# 2.net
KiCad netlist of a schematic drawn in Altium Designer
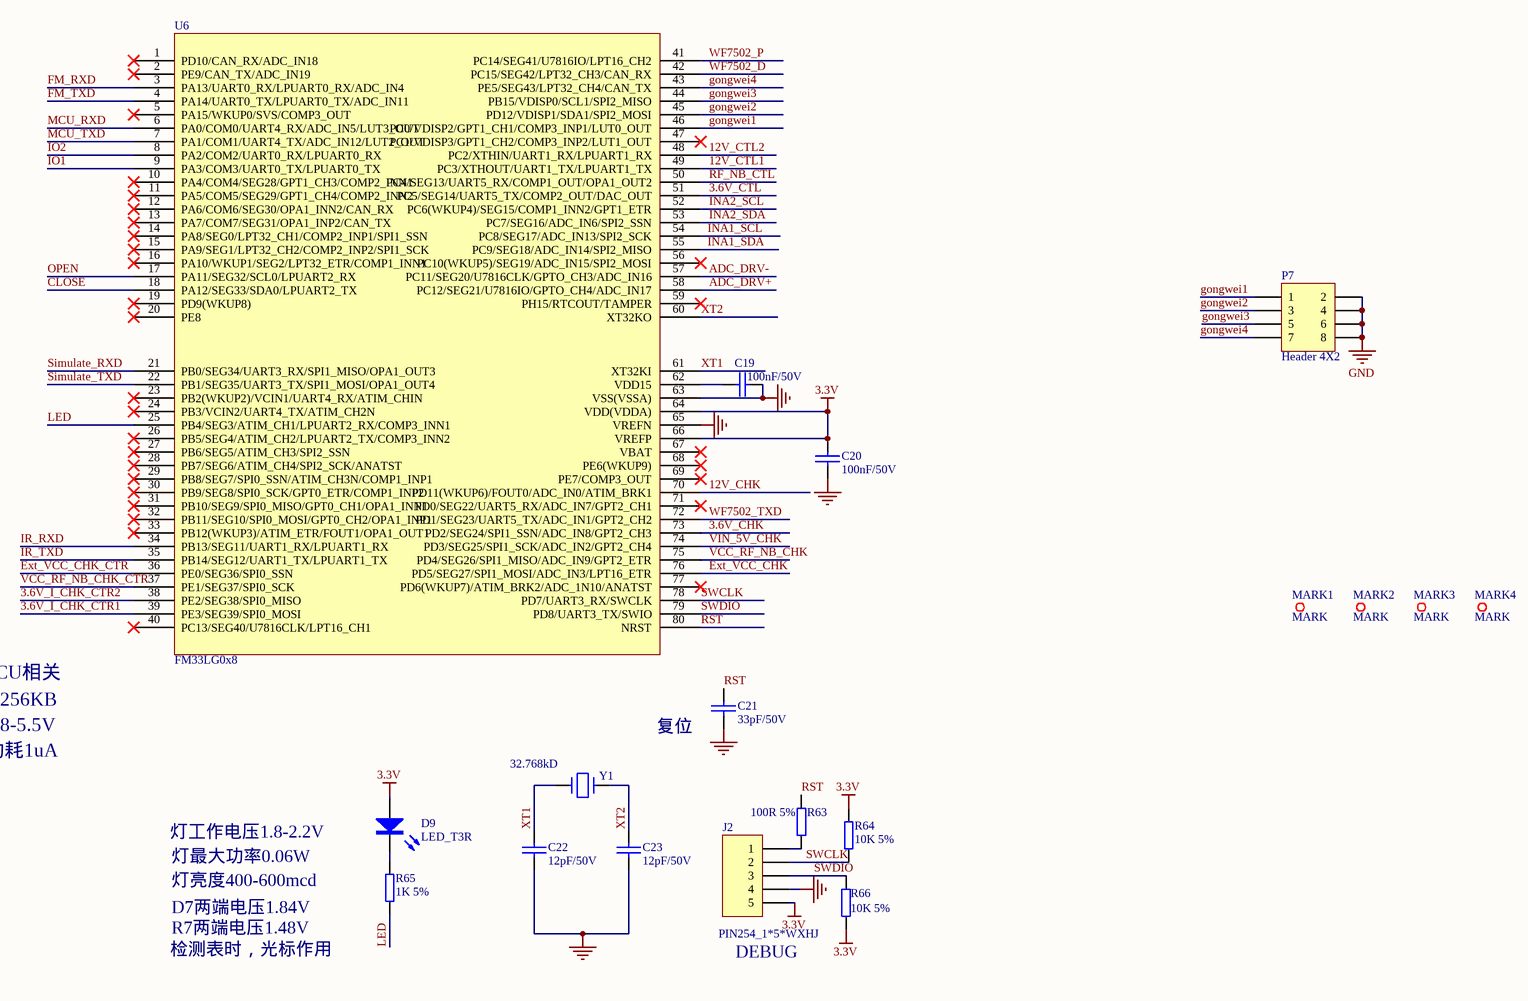
[diagram p0: 水表通用工装一版2.SchDoc]

(export (version "E")
  (design (tool "Eeschema 10.0.6"))
  (components
    (comp (ref "C19")
      (value "100nF/50V")
      (footprint "CAP0603")
      (description "104pF,50 V,±10%,0603,国巨,CC0603KRX7R9BB104")
      (fields (field (name "PART NUMBER") "101020103-0021"))
      (libsource (lib "Database_Libs2") (part "CC03K7R9_100N"))
    )
    (comp (ref "C20")
      (value "100nF/50V")
      (footprint "CAP0603")
      (description "104pF,50 V,±10%,0603,国巨,CC0603KRX7R9BB104")
      (fields (field (name "PART NUMBER") "101020103-0021"))
      (libsource (lib "Database_Libs2") (part "CC03K7R9_100N"))
    )
    (comp (ref "C21")
      (value "33pF/50V")
      (footprint "CAP0603")
      (description "33pF,50 V,±10%,0603,国巨,CC0603KRNPO9BN33")
      (fields (field (name "PART NUMBER") "101020103-0027"))
      (libsource (lib "Database_Libs2") (part "CC03KPO9_33P"))
    )
    (comp (ref "C22")
      (value "12pF/50V")
      (footprint "CAP0603")
      (description "12P,50 V,±5%,0603,国巨,CC0603JRNPO9BN12")
      (fields (field (name "PART NUMBER") "101020103-0005"))
      (libsource (lib "Database_Libs2") (part "CC03JPO9_12P"))
    )
    (comp (ref "C23")
      (value "12pF/50V")
      (footprint "CAP0603")
      (description "12P,50 V,±5%,0603,国巨,CC0603JRNPO9BN12")
      (fields (field (name "PART NUMBER") "101020103-0005"))
      (libsource (lib "Database_Libs2") (part "CC03JPO9_12P"))
    )
    (comp (ref "D9")
      (value "LED_T3R")
      (footprint "LED2_300")
      (description "圆形插件,3mm 圆形,插件,红光,湖北匡通电子有限公司,3BB4HC")
      (fields (field (name "PART NUMBER") "101040102-0001"))
      (libsource (lib "Database_Libs2") (part "01-LED_T3R"))
    )
    (comp (ref "J2")
      (value "PIN254_1*5*WXHJ")
      (footprint "PIN254_1*5*1100S")
      (description "1*5 ，Φ1.0 ，2.54mm，直脚,无需焊接器件")
      (fields (field (name "PART NUMBER") "AD_WXHJ_PinHeader_02"))
      (libsource (lib "Database_Libs2") (part "PIN254_1*5*1100S"))
    )
    (comp (ref "MARK1")
      (value "MARK")
      (footprint "MARK")
      (description "MARK点")
      (fields (field (name "PART NUMBER") "AD_WXHJ_MARK_01"))
      (libsource (lib "转接板封装") (part "MARK"))
    )
    (comp (ref "MARK2")
      (value "MARK")
      (footprint "MARK")
      (description "MARK点")
      (fields (field (name "PART NUMBER") "AD_WXHJ_MARK_01"))
      (libsource (lib "转接板封装") (part "MARK"))
    )
    (comp (ref "MARK3")
      (value "MARK")
      (footprint "MARK")
      (description "MARK点")
      (fields (field (name "PART NUMBER") "AD_WXHJ_MARK_01"))
      (libsource (lib "转接板封装") (part "MARK"))
    )
    (comp (ref "MARK4")
      (value "MARK")
      (footprint "MARK")
      (description "MARK点")
      (fields (field (name "PART NUMBER") "AD_WXHJ_MARK_01"))
      (libsource (lib "转接板封装") (part "MARK"))
    )
    (comp (ref "P7")
      (value "Header 4X2")
      (footprint "HDR2X4")
      (description "Header, 4-Pin, Dual row")
      (libsource (lib "CBB_Lib_SCH") (part "Header 4X2"))
    )
    (comp (ref "R63")
      (value "100R 5%")
      (footprint "RES0603")
      (description "100R,±5%,1/10W,0603,国巨,RC0603JR-07100RL")
      (fields (field (name "PART NUMBER") "101010103-0022"))
      (libsource (lib "Database_Libs2") (part "RC03J_100R"))
    )
    (comp (ref "R64")
      (value "10K 5%")
      (footprint "RES0603")
      (description "国巨,±5%,0603,,155 ℃,-55 ℃,RC0603JR-0710KL,无铅,200 ppm/℃,1/10W,,10K")
      (fields (field (name "PART NUMBER") "101010103-0003"))
      (libsource (lib "Database_Libs2") (part "RC03J_10K"))
    )
    (comp (ref "R65")
      (value "1K 5%")
      (footprint "RES0603")
      (description "1K,±5%,1/10W,0603,国巨,RC0603JR-071KL")
      (fields (field (name "PART NUMBER") "101010103-0008"))
      (libsource (lib "Database_Libs2") (part "RC03J_1K"))
    )
    (comp (ref "R66")
      (value "10K 5%")
      (footprint "RES0603")
      (description "国巨,±5%,0603,,155 ℃,-55 ℃,RC0603JR-0710KL,无铅,200 ppm/℃,1/10W,,10K")
      (fields (field (name "PART NUMBER") "101010103-0003"))
      (libsource (lib "Database_Libs2") (part "RC03J_10K"))
    )
    (comp (ref "U6") (value "FM33LG0x8") (footprint "LQFP80") (libsource (lib "FM_MCU") (part "FM33LG0x8")))
    (comp (ref "Y1")
      (value "32.768kD")
      (footprint "SMD-3215_2P")
      (fields (field (name "PART NUMBER") "1010601-0020"))
      (libsource (lib "Database_Libs2") (part "04_XTALSG12MD_32.768kD"))
    )
  )
  (nets
    (net (code "1") (name "/3.6V_CHK") (class "Default")
      (node (ref "U6") (pin "73") (pinfunction "PD2/SEG24/SPI1_SSN/ADC_IN8/GPT2_CH3_73") (pintype "passive"))
    )
    (net (code "2") (name "/3.6V_CTL") (class "Default")
      (node (ref "U6") (pin "51") (pinfunction "PC5/SEG14/UART5_TX/COMP2_OUT/DAC_OUT_51") (pintype "passive"))
    )
    (net (code "3") (name "/3.6V_I_CHK_CTR1") (class "Default")
      (node (ref "U6") (pin "39") (pinfunction "PE3/SEG39/SPI0_MOSI_39") (pintype "passive"))
    )
    (net (code "4") (name "/3.6V_I_CHK_CTR2") (class "Default")
      (node (ref "U6") (pin "38") (pinfunction "PE2/SEG38/SPI0_MISO_38") (pintype "passive"))
    )
    (net (code "5") (name "/12V_CHK") (class "Default")
      (node (ref "U6") (pin "70") (pinfunction "PD11(WKUP6)/FOUT0/ADC_IN0/ATIM_BRK1_70") (pintype "passive"))
    )
    (net (code "6") (name "/12V_CTL1") (class "Default")
      (node (ref "U6") (pin "49") (pinfunction "PC3/XTHOUT/UART1_TX/LPUART1_TX_49") (pintype "passive"))
    )
    (net (code "7") (name "/12V_CTL2") (class "Default")
      (node (ref "U6") (pin "48") (pinfunction "PC2/XTHIN/UART1_RX/LPUART1_RX_48") (pintype "passive"))
    )
    (net (code "8") (name "/ADC_DRV+") (class "Default")
      (node (ref "U6") (pin "58") (pinfunction "PC12/SEG21/U7816IO/GPTO_CH4/ADC_IN17_58") (pintype "passive"))
    )
    (net (code "9") (name "/ADC_DRV-") (class "Default")
      (node (ref "U6") (pin "57") (pinfunction "PC11/SEG20/U7816CLK/GPTO_CH3/ADC_IN16_57") (pintype "passive"))
    )
    (net (code "10") (name "/CLOSE") (class "Default")
      (node (ref "U6") (pin "18") (pinfunction "PA12/SEG33/SDA0/LPUART2_TX_18") (pintype "passive"))
    )
    (net (code "11") (name "/Ext_VCC_CHK") (class "Default")
      (node (ref "U6") (pin "76") (pinfunction "PD5/SEG27/SPI1_MOSI/ADC_IN3/LPT16_ETR_76") (pintype "passive"))
    )
    (net (code "12") (name "/Ext_VCC_CHK_CTR") (class "Default")
      (node (ref "U6") (pin "36") (pinfunction "PE0/SEG36/SPI0_SSN_36") (pintype "passive"))
    )
    (net (code "13") (name "/FM_RXD") (class "Default")
      (node (ref "U6") (pin "3") (pinfunction "PA13/UART0_RX/LPUART0_RX/ADC_IN4_3") (pintype "passive"))
    )
    (net (code "14") (name "/FM_TXD") (class "Default")
      (node (ref "U6") (pin "4") (pinfunction "PA14/UART0_TX/LPUART0_TX/ADC_IN11_4") (pintype "passive"))
    )
    (net (code "15") (name "/INA1_SCL") (class "Default")
      (node (ref "U6") (pin "54") (pinfunction "PC8/SEG17/ADC_IN13/SPI2_SCK_54") (pintype "passive"))
    )
    (net (code "16") (name "/INA1_SDA") (class "Default")
      (node (ref "U6") (pin "55") (pinfunction "PC9/SEG18/ADC_IN14/SPI2_MISO_55") (pintype "passive"))
    )
    (net (code "17") (name "/INA2_SCL") (class "Default")
      (node (ref "U6") (pin "52") (pinfunction "PC6(WKUP4)/SEG15/COMP1_INN2/GPT1_ETR_52") (pintype "passive"))
    )
    (net (code "18") (name "/INA2_SDA") (class "Default")
      (node (ref "U6") (pin "53") (pinfunction "PC7/SEG16/ADC_IN6/SPI2_SSN_53") (pintype "passive"))
    )
    (net (code "19") (name "/IO1") (class "Default")
      (node (ref "U6") (pin "9") (pinfunction "PA3/COM3/UART0_TX/LPUART0_TX_9") (pintype "passive"))
    )
    (net (code "20") (name "/IO2") (class "Default")
      (node (ref "U6") (pin "8") (pinfunction "PA2/COM2/UART0_RX/LPUART0_RX_8") (pintype "passive"))
    )
    (net (code "21") (name "/IR_RXD") (class "Default")
      (node (ref "U6") (pin "34") (pinfunction "PB13/SEG11/UART1_RX/LPUART1_RX_34") (pintype "passive"))
    )
    (net (code "22") (name "/IR_TXD") (class "Default")
      (node (ref "U6") (pin "35") (pinfunction "PB14/SEG12/UART1_TX/LPUART1_TX_35") (pintype "passive"))
    )
    (net (code "23") (name "/LED") (class "Default")
      (node (ref "R65") (pin "1") (pinfunction "1_1") (pintype "passive"))
      (node (ref "U6") (pin "25") (pinfunction "PB4/SEG3/ATIM_CH1/LPUART2_RX/COMP3_INN1_25") (pintype "passive"))
    )
    (net (code "24") (name "/MCU_RXD") (class "Default")
      (node (ref "U6") (pin "6") (pinfunction "PA0/COM0/UART4_RX/ADC_IN5/LUT3_OUT_6") (pintype "passive"))
    )
    (net (code "25") (name "/MCU_TXD") (class "Default")
      (node (ref "U6") (pin "7") (pinfunction "PA1/COM1/UART4_TX/ADC_IN12/LUT2_OUT_7") (pintype "passive"))
    )
    (net (code "26") (name "/OPEN") (class "Default")
      (node (ref "U6") (pin "17") (pinfunction "PA11/SEG32/SCL0/LPUART2_RX_17") (pintype "passive"))
    )
    (net (code "27") (name "/RF_NB_CTL") (class "Default")
      (node (ref "U6") (pin "50") (pinfunction "PC4/SEG13/UART5_RX/COMP1_OUT/OPA1_OUT2_50") (pintype "passive"))
    )
    (net (code "28") (name "/RST") (class "Default")
      (node (ref "C21") (pin "1") (pinfunction "1_1") (pintype "passive"))
      (node (ref "R63") (pin "1") (pinfunction "1_1") (pintype "passive"))
      (node (ref "U6") (pin "80") (pinfunction "NRST_80") (pintype "passive"))
    )
    (net (code "29") (name "/SWCLK") (class "Default")
      (node (ref "J2") (pin "2") (pinfunction "2_2") (pintype "passive"))
      (node (ref "R64") (pin "2") (pinfunction "2_2") (pintype "passive"))
      (node (ref "U6") (pin "78") (pinfunction "PD7/UART3_RX/SWCLK_78") (pintype "passive"))
    )
    (net (code "30") (name "/SWDIO") (class "Default")
      (node (ref "J2") (pin "3") (pinfunction "3_3") (pintype "passive"))
      (node (ref "R66") (pin "2") (pinfunction "2_2") (pintype "passive"))
      (node (ref "U6") (pin "79") (pinfunction "PD8/UART3_TX/SWIO_79") (pintype "passive"))
    )
    (net (code "31") (name "/Simulate_RXD") (class "Default")
      (node (ref "U6") (pin "21") (pinfunction "PB0/SEG34/UART3_RX/SPI1_MISO/OPA1_OUT3_21") (pintype "passive"))
    )
    (net (code "32") (name "/Simulate_TXD") (class "Default")
      (node (ref "U6") (pin "22") (pinfunction "PB1/SEG35/UART3_TX/SPI1_MOSI/OPA1_OUT4_22") (pintype "passive"))
    )
    (net (code "33") (name "/VCC_RF_NB_CHK") (class "Default")
      (node (ref "U6") (pin "75") (pinfunction "PD4/SEG26/SPI1_MISO/ADC_IN9/GPT2_ETR_75") (pintype "passive"))
    )
    (net (code "34") (name "/VCC_RF_NB_CHK_CTR") (class "Default")
      (node (ref "U6") (pin "37") (pinfunction "PE1/SEG37/SPI0_SCK_37") (pintype "passive"))
    )
    (net (code "35") (name "/VIN_5V_CHK") (class "Default")
      (node (ref "U6") (pin "74") (pinfunction "PD3/SEG25/SPI1_SCK/ADC_IN2/GPT2_CH4_74") (pintype "passive"))
    )
    (net (code "36") (name "/WF7502_D") (class "Default")
      (node (ref "U6") (pin "42") (pinfunction "PC15/SEG42/LPT32_CH3/CAN_RX_42") (pintype "passive"))
    )
    (net (code "37") (name "/WF7502_P") (class "Default")
      (node (ref "U6") (pin "41") (pinfunction "PC14/SEG41/U7816IO/LPT16_CH2_41") (pintype "passive"))
    )
    (net (code "38") (name "/WF7502_TXD") (class "Default")
      (node (ref "U6") (pin "72") (pinfunction "PD1/SEG23/UART5_TX/ADC_IN1/GPT2_CH2_72") (pintype "passive"))
    )
    (net (code "39") (name "/XT1") (class "Default")
      (node (ref "C22") (pin "1") (pinfunction "1_1") (pintype "passive"))
      (node (ref "U6") (pin "61") (pinfunction "XT32KI_61") (pintype "passive"))
      (node (ref "Y1") (pin "1") (pinfunction "1_1") (pintype "passive"))
    )
    (net (code "40") (name "/XT2") (class "Default")
      (node (ref "C23") (pin "2") (pinfunction "2_2") (pintype "passive"))
      (node (ref "U6") (pin "60") (pinfunction "XT32KO_60") (pintype "passive"))
      (node (ref "Y1") (pin "2") (pinfunction "2_2") (pintype "passive"))
    )
    (net (code "41") (name "/gongwei1") (class "Default")
      (node (ref "P7") (pin "1") (pinfunction "1_1") (pintype "passive"))
      (node (ref "U6") (pin "46") (pinfunction "PC0/VDISP2/GPT1_CH1/COMP3_INP1/LUT0_OUT_46") (pintype "passive"))
    )
    (net (code "42") (name "/gongwei2") (class "Default")
      (node (ref "P7") (pin "3") (pinfunction "3_3") (pintype "passive"))
      (node (ref "U6") (pin "45") (pinfunction "PD12/VDISP1/SDA1/SPI2_MOSI_45") (pintype "passive"))
    )
    (net (code "43") (name "/gongwei3") (class "Default")
      (node (ref "P7") (pin "5") (pinfunction "5_5") (pintype "passive"))
      (node (ref "U6") (pin "44") (pinfunction "PB15/VDISP0/SCL1/SPI2_MISO_44") (pintype "passive"))
    )
    (net (code "44") (name "/gongwei4") (class "Default")
      (node (ref "P7") (pin "7") (pinfunction "7_7") (pintype "passive"))
      (node (ref "U6") (pin "43") (pinfunction "PE5/SEG43/LPT32_CH4/CAN_TX_43") (pintype "passive"))
    )
    (net (code "45") (name "3.3V") (class "Default")
      (node (ref "C20") (pin "2") (pinfunction "2_2") (pintype "passive"))
      (node (ref "D9") (pin "1") (pinfunction "1_1") (pintype "passive"))
      (node (ref "J2") (pin "5") (pinfunction "5_5") (pintype "passive"))
      (node (ref "R64") (pin "1") (pinfunction "1_1") (pintype "passive"))
      (node (ref "R66") (pin "1") (pinfunction "1_1") (pintype "passive"))
      (node (ref "U6") (pin "64") (pinfunction "VDD(VDDA)_64") (pintype "passive"))
      (node (ref "U6") (pin "66") (pinfunction "VREFP_66") (pintype "passive"))
    )
    (net (code "46") (name "GND") (class "Default")
      (node (ref "C19") (pin "2") (pinfunction "2_2") (pintype "passive"))
      (node (ref "C20") (pin "1") (pinfunction "1_1") (pintype "passive"))
      (node (ref "C21") (pin "2") (pinfunction "2_2") (pintype "passive"))
      (node (ref "C22") (pin "2") (pinfunction "2_2") (pintype "passive"))
      (node (ref "C23") (pin "1") (pinfunction "1_1") (pintype "passive"))
      (node (ref "J2") (pin "4") (pinfunction "4_4") (pintype "passive"))
      (node (ref "P7") (pin "2") (pinfunction "2_2") (pintype "passive"))
      (node (ref "P7") (pin "4") (pinfunction "4_4") (pintype "passive"))
      (node (ref "P7") (pin "6") (pinfunction "6_6") (pintype "passive"))
      (node (ref "P7") (pin "8") (pinfunction "8_8") (pintype "passive"))
      (node (ref "U6") (pin "63") (pinfunction "VSS(VSSA)_63") (pintype "passive"))
      (node (ref "U6") (pin "65") (pinfunction "VREFN_65") (pintype "passive"))
    )
    (net (code "47") (name "Net-(D9-Pad2)") (class "Default")
      (node (ref "D9") (pin "2") (pinfunction "2_2") (pintype "passive"))
      (node (ref "R65") (pin "2") (pinfunction "2_2") (pintype "passive"))
    )
    (net (code "48") (name "Net-(J2-Pad1)") (class "Default")
      (node (ref "J2") (pin "1") (pinfunction "1_1") (pintype "passive"))
      (node (ref "R63") (pin "2") (pinfunction "2_2") (pintype "passive"))
    )
    (net (code "49") (name "Net-(U6-VDD15)") (class "Default")
      (node (ref "C19") (pin "1") (pinfunction "1_1") (pintype "passive"))
      (node (ref "U6") (pin "62") (pinfunction "VDD15_62") (pintype "passive"))
    )
    (net (code "50") (name "unconnected-(U6-PA4{slash}COM4{slash}SEG28{slash}GPT1_CH3{slash}COMP2_INN1-Pad10)") (class "Default")
      (node (ref "U6") (pin "10") (pinfunction "PA4/COM4/SEG28/GPT1_CH3/COMP2_INN1_10") (pintype "passive+no_connect"))
    )
    (net (code "51") (name "unconnected-(U6-PA5{slash}COM5{slash}SEG29{slash}GPT1_CH4{slash}COMP2_INN2-Pad11)") (class "Default")
      (node (ref "U6") (pin "11") (pinfunction "PA5/COM5/SEG29/GPT1_CH4/COMP2_INN2_11") (pintype "passive+no_connect"))
    )
    (net (code "52") (name "unconnected-(U6-PA6{slash}COM6{slash}SEG30{slash}OPA1_INN2{slash}CAN_RX-Pad12)") (class "Default")
      (node (ref "U6") (pin "12") (pinfunction "PA6/COM6/SEG30/OPA1_INN2/CAN_RX_12") (pintype "passive+no_connect"))
    )
    (net (code "53") (name "unconnected-(U6-PA7{slash}COM7{slash}SEG31{slash}OPA1_INP2{slash}CAN_TX-Pad13)") (class "Default")
      (node (ref "U6") (pin "13") (pinfunction "PA7/COM7/SEG31/OPA1_INP2/CAN_TX_13") (pintype "passive+no_connect"))
    )
    (net (code "54") (name "unconnected-(U6-PA8{slash}SEG0{slash}LPT32_CH1{slash}COMP2_INP1{slash}SPI1_SSN-Pad14)") (class "Default")
      (node (ref "U6") (pin "14") (pinfunction "PA8/SEG0/LPT32_CH1/COMP2_INP1/SPI1_SSN_14") (pintype "passive+no_connect"))
    )
    (net (code "55") (name "unconnected-(U6-PA9{slash}SEG1{slash}LPT32_CH2{slash}COMP2_INP2{slash}SPI1_SCK-Pad15)") (class "Default")
      (node (ref "U6") (pin "15") (pinfunction "PA9/SEG1/LPT32_CH2/COMP2_INP2/SPI1_SCK_15") (pintype "passive+no_connect"))
    )
    (net (code "56") (name "unconnected-(U6-PA10{slash}WKUP1{slash}SEG2{slash}LPT32_ETR{slash}COMP1_INN1-Pad16)") (class "Default")
      (node (ref "U6") (pin "16") (pinfunction "PA10/WKUP1/SEG2/LPT32_ETR/COMP1_INN1_16") (pintype "passive+no_connect"))
    )
    (net (code "57") (name "unconnected-(U6-PA15{slash}WKUP0{slash}SVS{slash}COMP3_OUT-Pad5)") (class "Default")
      (node (ref "U6") (pin "5") (pinfunction "PA15/WKUP0/SVS/COMP3_OUT_5") (pintype "passive+no_connect"))
    )
    (net (code "58") (name "unconnected-(U6-PB2(WKUP2){slash}VCIN1{slash}UART4_RX{slash}ATIM_CHIN-Pad23)") (class "Default")
      (node (ref "U6") (pin "23") (pinfunction "PB2(WKUP2)/VCIN1/UART4_RX/ATIM_CHIN_23") (pintype "passive+no_connect"))
    )
    (net (code "59") (name "unconnected-(U6-PB3{slash}VCIN2{slash}UART4_TX{slash}ATIM_CH2N-Pad24)") (class "Default")
      (node (ref "U6") (pin "24") (pinfunction "PB3/VCIN2/UART4_TX/ATIM_CH2N_24") (pintype "passive+no_connect"))
    )
    (net (code "60") (name "unconnected-(U6-PB5{slash}SEG4{slash}ATIM_CH2{slash}LPUART2_TX{slash}COMP3_INN2-Pad26)") (class "Default")
      (node (ref "U6") (pin "26") (pinfunction "PB5/SEG4/ATIM_CH2/LPUART2_TX/COMP3_INN2_26") (pintype "passive+no_connect"))
    )
    (net (code "61") (name "unconnected-(U6-PB6{slash}SEG5{slash}ATIM_CH3{slash}SPI2_SSN-Pad27)") (class "Default")
      (node (ref "U6") (pin "27") (pinfunction "PB6/SEG5/ATIM_CH3/SPI2_SSN_27") (pintype "passive+no_connect"))
    )
    (net (code "62") (name "unconnected-(U6-PB7{slash}SEG6{slash}ATIM_CH4{slash}SPI2_SCK{slash}ANATST-Pad28)") (class "Default")
      (node (ref "U6") (pin "28") (pinfunction "PB7/SEG6/ATIM_CH4/SPI2_SCK/ANATST_28") (pintype "passive+no_connect"))
    )
    (net (code "63") (name "unconnected-(U6-PB8{slash}SEG7{slash}SPI0_SSN{slash}ATIM_CH3N{slash}COMP1_INP1-Pad29)") (class "Default")
      (node (ref "U6") (pin "29") (pinfunction "PB8/SEG7/SPI0_SSN/ATIM_CH3N/COMP1_INP1_29") (pintype "passive+no_connect"))
    )
    (net (code "64") (name "unconnected-(U6-PB9{slash}SEG8{slash}SPI0_SCK{slash}GPT0_ETR{slash}COMP1_INP2-Pad30)") (class "Default")
      (node (ref "U6") (pin "30") (pinfunction "PB9/SEG8/SPI0_SCK/GPT0_ETR/COMP1_INP2_30") (pintype "passive+no_connect"))
    )
    (net (code "65") (name "unconnected-(U6-PB10{slash}SEG9{slash}SPI0_MISO{slash}GPT0_CH1{slash}OPA1_INN1-Pad31)") (class "Default")
      (node (ref "U6") (pin "31") (pinfunction "PB10/SEG9/SPI0_MISO/GPT0_CH1/OPA1_INN1_31") (pintype "passive+no_connect"))
    )
    (net (code "66") (name "unconnected-(U6-PB11{slash}SEG10{slash}SPI0_MOSI{slash}GPT0_CH2{slash}OPA1_INP1-Pad32)") (class "Default")
      (node (ref "U6") (pin "32") (pinfunction "PB11/SEG10/SPI0_MOSI/GPT0_CH2/OPA1_INP1_32") (pintype "passive+no_connect"))
    )
    (net (code "67") (name "unconnected-(U6-PB12(WKUP3){slash}ATIM_ETR{slash}FOUT1{slash}OPA1_OUT1-Pad33)") (class "Default")
      (node (ref "U6") (pin "33") (pinfunction "PB12(WKUP3)/ATIM_ETR/FOUT1/OPA1_OUT1_33") (pintype "passive+no_connect"))
    )
    (net (code "68") (name "unconnected-(U6-PC1{slash}VDISP3{slash}GPT1_CH2{slash}COMP3_INP2{slash}LUT1_OUT-Pad47)") (class "Default")
      (node (ref "U6") (pin "47") (pinfunction "PC1/VDISP3/GPT1_CH2/COMP3_INP2/LUT1_OUT_47") (pintype "passive+no_connect"))
    )
    (net (code "69") (name "unconnected-(U6-PC10(WKUP5){slash}SEG19{slash}ADC_IN15{slash}SPI2_MOSI-Pad56)") (class "Default")
      (node (ref "U6") (pin "56") (pinfunction "PC10(WKUP5)/SEG19/ADC_IN15/SPI2_MOSI_56") (pintype "passive+no_connect"))
    )
    (net (code "70") (name "unconnected-(U6-PC13{slash}SEG40{slash}U7816CLK{slash}LPT16_CH1-Pad40)") (class "Default")
      (node (ref "U6") (pin "40") (pinfunction "PC13/SEG40/U7816CLK/LPT16_CH1_40") (pintype "passive+no_connect"))
    )
    (net (code "71") (name "unconnected-(U6-PD0{slash}SEG22{slash}UART5_RX{slash}ADC_IN7{slash}GPT2_CH1-Pad71)") (class "Default")
      (node (ref "U6") (pin "71") (pinfunction "PD0/SEG22/UART5_RX/ADC_IN7/GPT2_CH1_71") (pintype "passive+no_connect"))
    )
    (net (code "72") (name "unconnected-(U6-PD6(WKUP7){slash}ATIM_BRK2{slash}ADC_1N10{slash}ANATST-Pad77)") (class "Default")
      (node (ref "U6") (pin "77") (pinfunction "PD6(WKUP7)/ATIM_BRK2/ADC_1N10/ANATST_77") (pintype "passive+no_connect"))
    )
    (net (code "73") (name "unconnected-(U6-PD9(WKUP8)-Pad19)") (class "Default")
      (node (ref "U6") (pin "19") (pinfunction "PD9(WKUP8)_19") (pintype "passive+no_connect"))
    )
    (net (code "74") (name "unconnected-(U6-PD10{slash}CAN_RX{slash}ADC_IN18-Pad1)") (class "Default")
      (node (ref "U6") (pin "1") (pinfunction "PD10/CAN_RX/ADC_IN18_1") (pintype "passive+no_connect"))
    )
    (net (code "75") (name "unconnected-(U6-PE6(WKUP9)-Pad68)") (class "Default")
      (node (ref "U6") (pin "68") (pinfunction "PE6(WKUP9)_68") (pintype "passive+no_connect"))
    )
    (net (code "76") (name "unconnected-(U6-PE7{slash}COMP3_OUT-Pad69)") (class "Default")
      (node (ref "U6") (pin "69") (pinfunction "PE7/COMP3_OUT_69") (pintype "passive+no_connect"))
    )
    (net (code "77") (name "unconnected-(U6-PE8-Pad20)") (class "Default")
      (node (ref "U6") (pin "20") (pinfunction "PE8_20") (pintype "passive+no_connect"))
    )
    (net (code "78") (name "unconnected-(U6-PE9{slash}CAN_TX{slash}ADC_IN19-Pad2)") (class "Default")
      (node (ref "U6") (pin "2") (pinfunction "PE9/CAN_TX/ADC_IN19_2") (pintype "passive+no_connect"))
    )
    (net (code "79") (name "unconnected-(U6-PH15{slash}RTCOUT{slash}TAMPER-Pad59)") (class "Default")
      (node (ref "U6") (pin "59") (pinfunction "PH15/RTCOUT/TAMPER_59") (pintype "passive+no_connect"))
    )
    (net (code "80") (name "unconnected-(U6-VBAT-Pad67)") (class "Default")
      (node (ref "U6") (pin "67") (pinfunction "VBAT_67") (pintype "passive+no_connect"))
    )
  )
)
